# audible.net
KiCad netlist of a schematic drawn in EAGLE
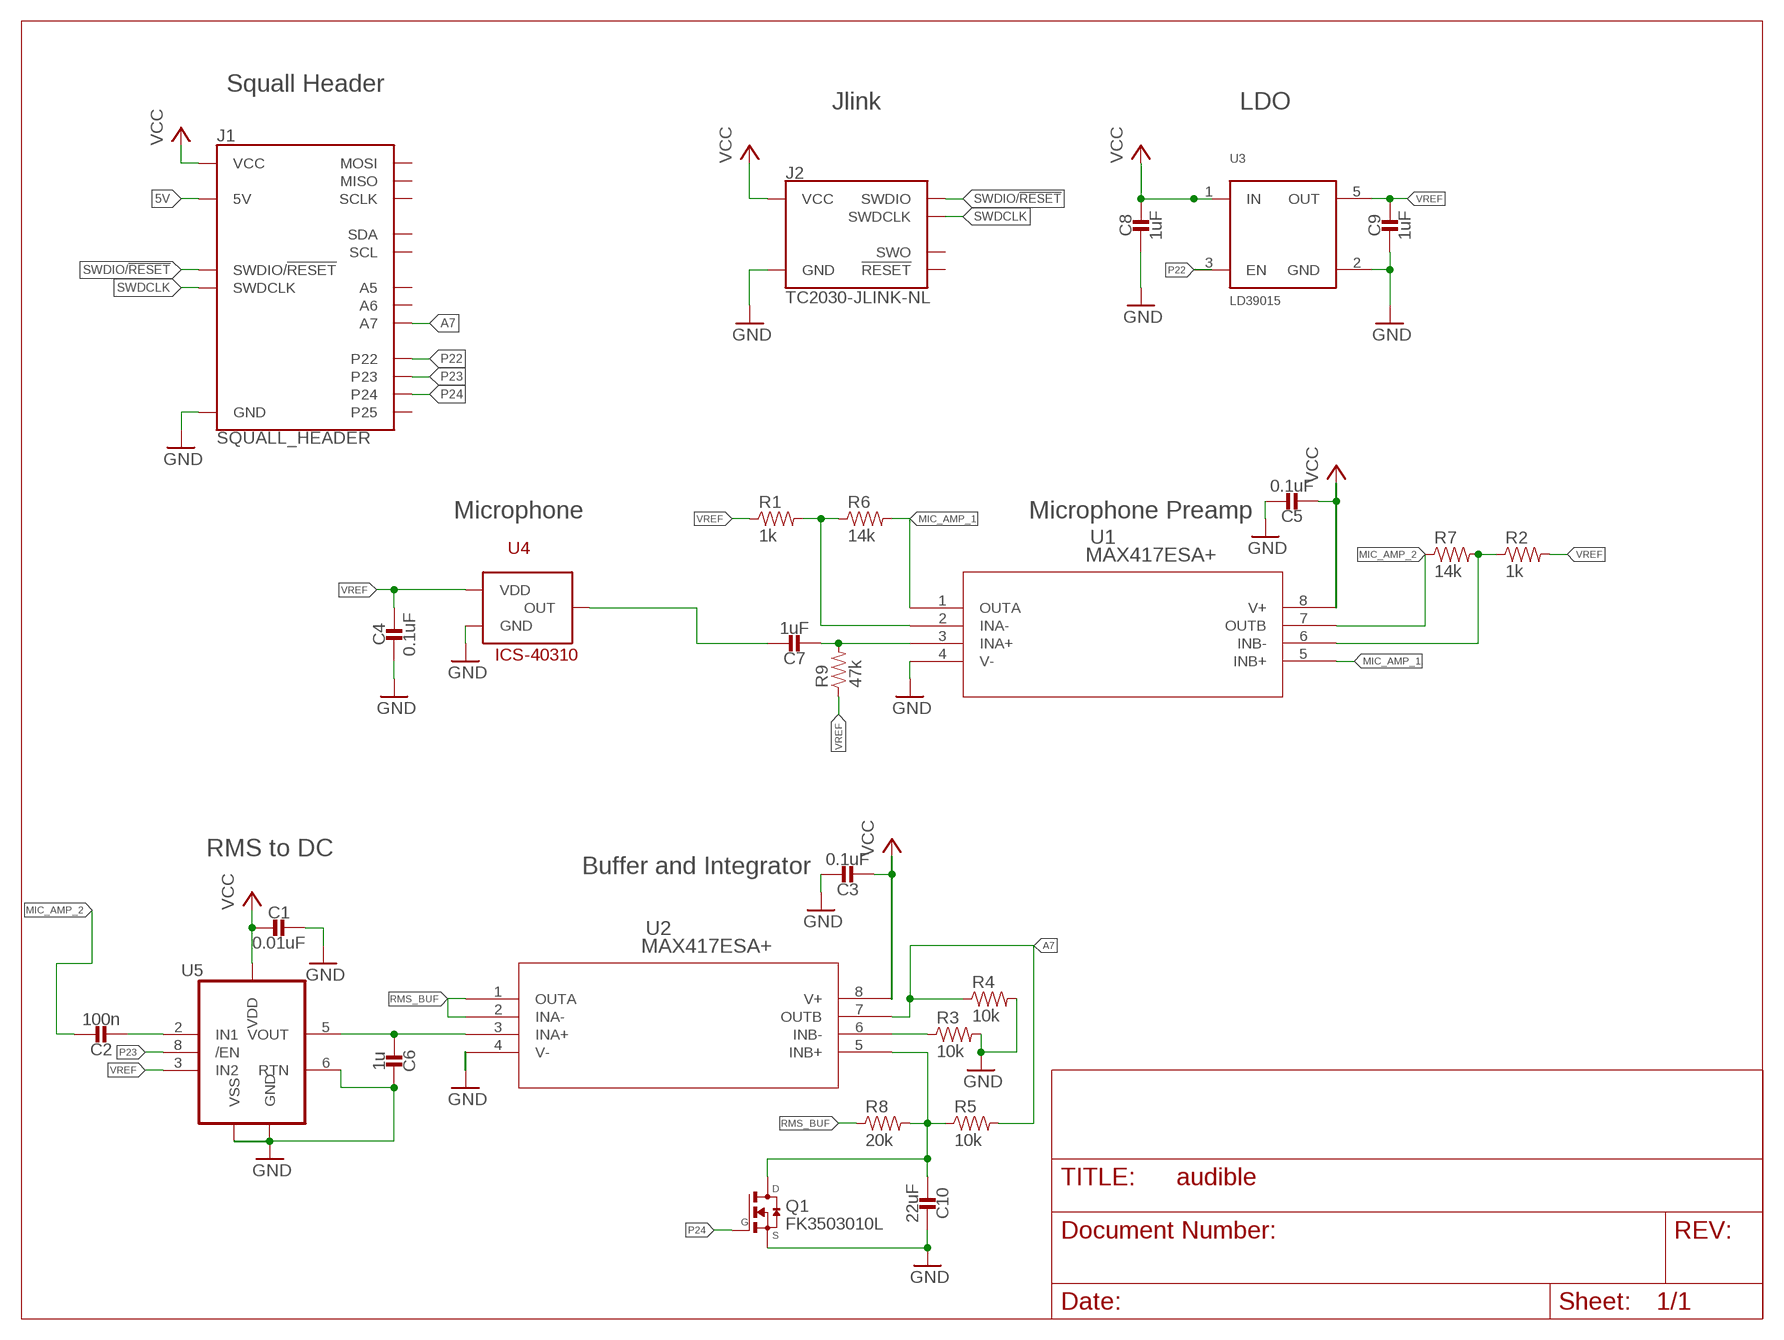
[diagram p0: schematic, sheet 1]

(export (version "E")
  (design (tool "Eeschema 10.0.6"))
  (components
    (comp (ref "C1")
      (value "0.01uF")
      (footprint "eagle-import:0402_CAP")
      (libsource (lib "eagle-import") (part "CAPACITOR"))
    )
    (comp (ref "C2")
      (value "100n")
      (footprint "eagle-import:0402_CAP")
      (libsource (lib "eagle-import") (part "CAPACITOR"))
    )
    (comp (ref "C3")
      (value "0.1uF")
      (footprint "eagle-import:0402_CAP")
      (libsource (lib "eagle-import") (part "CAPACITOR"))
    )
    (comp (ref "C4")
      (value "0.1uF")
      (footprint "eagle-import:0402_CAP")
      (libsource (lib "eagle-import") (part "CAPACITOR"))
    )
    (comp (ref "C5")
      (value "0.1uF")
      (footprint "eagle-import:0402_CAP")
      (libsource (lib "eagle-import") (part "CAPACITOR"))
    )
    (comp (ref "C6")
      (value "1u")
      (footprint "eagle-import:0402_CAP")
      (libsource (lib "eagle-import") (part "CAPACITOR"))
    )
    (comp (ref "C7")
      (value "1uF")
      (footprint "eagle-import:0402_CAP")
      (libsource (lib "eagle-import") (part "CAPACITOR"))
    )
    (comp (ref "C8")
      (value "1uF")
      (footprint "eagle-import:0402_CAP")
      (libsource (lib "eagle-import") (part "CAPACITOR"))
    )
    (comp (ref "C9")
      (value "1uF")
      (footprint "eagle-import:0402_CAP")
      (libsource (lib "eagle-import") (part "CAPACITOR"))
    )
    (comp (ref "C10")
      (value "22uF")
      (footprint "eagle-import:0402_CAP")
      (libsource (lib "eagle-import") (part "CAPACITOR"))
    )
    (comp (ref "J1")
      (value "SQUALL_HEADER")
      (footprint "eagle-import:SQUALL_HEADER")
      (libsource (lib "eagle-import") (part "SQUALL_HEADER"))
    )
    (comp (ref "J2")
      (value "TC2030-JLINK-NL")
      (footprint "eagle-import:TC2030-IDC-NL")
      (libsource (lib "eagle-import") (part "TC2030-JLINK-NL"))
    )
    (comp (ref "Q1")
      (value "FK3503010L")
      (footprint "eagle-import:SC85")
      (libsource (lib "eagle-import") (part "FK3503010L"))
    )
    (comp (ref "R1")
      (value "1k")
      (footprint "eagle-import:0402_RES")
      (libsource (lib "eagle-import") (part "RESISTOR0402_RES"))
    )
    (comp (ref "R2")
      (value "1k")
      (footprint "eagle-import:0402_RES")
      (libsource (lib "eagle-import") (part "RESISTOR0402_RES"))
    )
    (comp (ref "R3")
      (value "10k")
      (footprint "eagle-import:0402_RES")
      (libsource (lib "eagle-import") (part "RESISTOR0402_RES"))
    )
    (comp (ref "R4")
      (value "10k")
      (footprint "eagle-import:0402_RES")
      (libsource (lib "eagle-import") (part "RESISTOR0402_RES"))
    )
    (comp (ref "R5")
      (value "10k")
      (footprint "eagle-import:0402_RES")
      (libsource (lib "eagle-import") (part "RESISTOR0402_RES"))
    )
    (comp (ref "R6")
      (value "14k")
      (footprint "eagle-import:0402_RES")
      (libsource (lib "eagle-import") (part "RESISTOR0402_RES"))
    )
    (comp (ref "R7")
      (value "14k")
      (footprint "eagle-import:0402_RES")
      (libsource (lib "eagle-import") (part "RESISTOR0402_RES"))
    )
    (comp (ref "R8")
      (value "20k")
      (footprint "eagle-import:0402_RES")
      (libsource (lib "eagle-import") (part "RESISTOR0402_RES"))
    )
    (comp (ref "R9")
      (value "47k")
      (footprint "eagle-import:0402_RES")
      (libsource (lib "eagle-import") (part "RESISTOR0402_RES"))
    )
    (comp (ref "U1")
      (value "MAX417ESA+")
      (footprint "eagle-import:21-0041B_8")
      (fields (field (name "MANUFACTURER_PART_NUMBER") "max417esa+"))
      (libsource (lib "eagle-import") (part "MAX417ESA+"))
    )
    (comp (ref "U2")
      (value "MAX417ESA+")
      (footprint "eagle-import:21-0041B_8")
      (fields (field (name "MANUFACTURER_PART_NUMBER") "max417esa+"))
      (libsource (lib "eagle-import") (part "MAX417ESA+"))
    )
    (comp (ref "U3")
      (value "LD39015")
      (footprint "eagle-import:SOT-23-5")
      (libsource (lib "eagle-import") (part "LD39015"))
    )
    (comp (ref "U4")
      (value "ICS-40310")
      (footprint "eagle-import:LGA_CAV3")
      (libsource (lib "eagle-import") (part "ICS-40310"))
    )
    (comp (ref "U5")
      (value "LTC1966CMS8")
      (footprint "eagle-import:MSOP8")
      (libsource (lib "eagle-import") (part "LTC1966MS8C"))
    )
  )
  (nets
    (net (code "1") (name "/SWDIO{slash}~{RESET}") (class "Default")
      (node (ref "J1") (pin "B4") (pinfunction "SWDIO/~{RESET}_B4") (pintype "bidirectional"))
      (node (ref "J2") (pin "2") (pinfunction "SWDIO_2") (pintype "bidirectional"))
    )
    (net (code "2") (name "5V") (class "Default")
      (node (ref "J1") (pin "A5") (pinfunction "5V_A5") (pintype "bidirectional"))
      (node (ref "J1") (pin "A7") (pinfunction "5V_A7") (pintype "bidirectional"))
    )
    (net (code "3") (name "A7") (class "Default")
      (node (ref "J1") (pin "B5") (pinfunction "A7_B5") (pintype "bidirectional"))
      (node (ref "R4") (pin "1") (pinfunction "1_1") (pintype "passive"))
      (node (ref "R5") (pin "2") (pinfunction "2_2") (pintype "passive"))
      (node (ref "U2") (pin "7") (pinfunction "OUTB_7") (pintype "output"))
    )
    (net (code "4") (name "GND") (class "Default")
      (node (ref "C1") (pin "1") (pinfunction "1_1") (pintype "bidirectional"))
      (node (ref "C10") (pin "1") (pinfunction "1_1") (pintype "bidirectional"))
      (node (ref "C3") (pin "1") (pinfunction "1_1") (pintype "bidirectional"))
      (node (ref "C4") (pin "2") (pinfunction "2_2") (pintype "bidirectional"))
      (node (ref "C5") (pin "1") (pinfunction "1_1") (pintype "bidirectional"))
      (node (ref "C6") (pin "1") (pinfunction "1_1") (pintype "bidirectional"))
      (node (ref "C8") (pin "2") (pinfunction "2_2") (pintype "bidirectional"))
      (node (ref "C9") (pin "2") (pinfunction "2_2") (pintype "bidirectional"))
      (node (ref "J1") (pin "A10") (pinfunction "GND_A10") (pintype "bidirectional"))
      (node (ref "J1") (pin "A9") (pinfunction "GND_A9") (pintype "bidirectional"))
      (node (ref "J2") (pin "5") (pinfunction "GND_5") (pintype "bidirectional"))
      (node (ref "Q1") (pin "2") (pinfunction "S_2") (pintype "passive"))
      (node (ref "R3") (pin "2") (pinfunction "2_2") (pintype "passive"))
      (node (ref "R4") (pin "2") (pinfunction "2_2") (pintype "passive"))
      (node (ref "U1") (pin "4") (pinfunction "V-_4") (pintype "power_in"))
      (node (ref "U2") (pin "4") (pinfunction "V-_4") (pintype "power_in"))
      (node (ref "U3") (pin "2") (pinfunction "GND_2") (pintype "bidirectional"))
      (node (ref "U4") (pin "P$2") (pinfunction "GND_P$2") (pintype "bidirectional"))
      (node (ref "U5") (pin "1") (pinfunction "GND_1") (pintype "bidirectional"))
      (node (ref "U5") (pin "4") (pinfunction "VSS_4") (pintype "bidirectional"))
      (node (ref "U5") (pin "6") (pinfunction "RTN_6") (pintype "passive"))
    )
    (net (code "5") (name "MIC_AMP_1") (class "Default")
      (node (ref "R6") (pin "2") (pinfunction "2_2") (pintype "passive"))
      (node (ref "U1") (pin "1") (pinfunction "OUTA_1") (pintype "output"))
      (node (ref "U1") (pin "5") (pinfunction "INB+_5") (pintype "input"))
    )
    (net (code "6") (name "MIC_AMP_2") (class "Default")
      (node (ref "C2") (pin "1") (pinfunction "1_1") (pintype "bidirectional"))
      (node (ref "R7") (pin "1") (pinfunction "1_1") (pintype "passive"))
      (node (ref "U1") (pin "7") (pinfunction "OUTB_7") (pintype "output"))
    )
    (net (code "7") (name "Net-(Q1-D)") (class "Default")
      (node (ref "C10") (pin "2") (pinfunction "2_2") (pintype "bidirectional"))
      (node (ref "Q1") (pin "3") (pinfunction "D_3") (pintype "passive"))
      (node (ref "R5") (pin "1") (pinfunction "1_1") (pintype "passive"))
      (node (ref "R8") (pin "2") (pinfunction "2_2") (pintype "passive"))
      (node (ref "U2") (pin "5") (pinfunction "INB+_5") (pintype "input"))
    )
    (net (code "8") (name "Net-(U1-INA+)") (class "Default")
      (node (ref "C7") (pin "2") (pinfunction "2_2") (pintype "bidirectional"))
      (node (ref "R9") (pin "2") (pinfunction "2_2") (pintype "passive"))
      (node (ref "U1") (pin "3") (pinfunction "INA+_3") (pintype "input"))
    )
    (net (code "9") (name "Net-(U1-INA-)") (class "Default")
      (node (ref "R1") (pin "2") (pinfunction "2_2") (pintype "passive"))
      (node (ref "R6") (pin "1") (pinfunction "1_1") (pintype "passive"))
      (node (ref "U1") (pin "2") (pinfunction "INA-_2") (pintype "input"))
    )
    (net (code "10") (name "Net-(U1-INB-)") (class "Default")
      (node (ref "R2") (pin "1") (pinfunction "1_1") (pintype "passive"))
      (node (ref "R7") (pin "2") (pinfunction "2_2") (pintype "passive"))
      (node (ref "U1") (pin "6") (pinfunction "INB-_6") (pintype "input"))
    )
    (net (code "11") (name "Net-(U2-INA+)") (class "Default")
      (node (ref "C6") (pin "2") (pinfunction "2_2") (pintype "bidirectional"))
      (node (ref "U2") (pin "3") (pinfunction "INA+_3") (pintype "input"))
      (node (ref "U5") (pin "5") (pinfunction "VOUT_5") (pintype "output"))
    )
    (net (code "12") (name "Net-(U2-INB-)") (class "Default")
      (node (ref "R3") (pin "1") (pinfunction "1_1") (pintype "passive"))
      (node (ref "U2") (pin "6") (pinfunction "INB-_6") (pintype "input"))
    )
    (net (code "13") (name "Net-(U4-OUT)") (class "Default")
      (node (ref "C7") (pin "1") (pinfunction "1_1") (pintype "bidirectional"))
      (node (ref "U4") (pin "P$1") (pinfunction "OUT_P$1") (pintype "bidirectional"))
    )
    (net (code "14") (name "Net-(U5-IN1)") (class "Default")
      (node (ref "C2") (pin "2") (pinfunction "2_2") (pintype "bidirectional"))
      (node (ref "U5") (pin "2") (pinfunction "IN1_2") (pintype "input"))
    )
    (net (code "15") (name "P22") (class "Default")
      (node (ref "J1") (pin "A2") (pinfunction "P22_A2") (pintype "bidirectional"))
      (node (ref "U3") (pin "3") (pinfunction "EN_3") (pintype "bidirectional"))
    )
    (net (code "16") (name "P23") (class "Default")
      (node (ref "J1") (pin "A4") (pinfunction "P23_A4") (pintype "bidirectional"))
      (node (ref "U5") (pin "8") (pinfunction "/EN_8") (pintype "input"))
    )
    (net (code "17") (name "P24") (class "Default")
      (node (ref "J1") (pin "A6") (pinfunction "P24_A6") (pintype "bidirectional"))
      (node (ref "Q1") (pin "1") (pinfunction "G_1") (pintype "passive"))
    )
    (net (code "18") (name "RMS_BUF") (class "Default")
      (node (ref "R8") (pin "1") (pinfunction "1_1") (pintype "passive"))
      (node (ref "U2") (pin "1") (pinfunction "OUTA_1") (pintype "output"))
      (node (ref "U2") (pin "2") (pinfunction "INA-_2") (pintype "input"))
    )
    (net (code "19") (name "SWDCLK") (class "Default")
      (node (ref "J1") (pin "B2") (pinfunction "SWDCLK_B2") (pintype "bidirectional"))
      (node (ref "J2") (pin "4") (pinfunction "SWDCLK_4") (pintype "bidirectional"))
    )
    (net (code "20") (name "VCC") (class "Default")
      (node (ref "C1") (pin "2") (pinfunction "2_2") (pintype "bidirectional"))
      (node (ref "C3") (pin "2") (pinfunction "2_2") (pintype "bidirectional"))
      (node (ref "C5") (pin "2") (pinfunction "2_2") (pintype "bidirectional"))
      (node (ref "C8") (pin "1") (pinfunction "1_1") (pintype "bidirectional"))
      (node (ref "J1") (pin "A1") (pinfunction "VCC_A1") (pintype "bidirectional"))
      (node (ref "J1") (pin "A3") (pinfunction "VCC_A3") (pintype "bidirectional"))
      (node (ref "J2") (pin "1") (pinfunction "VCC_1") (pintype "bidirectional"))
      (node (ref "U1") (pin "8") (pinfunction "V+_8") (pintype "power_in"))
      (node (ref "U2") (pin "8") (pinfunction "V+_8") (pintype "power_in"))
      (node (ref "U3") (pin "1") (pinfunction "IN_1") (pintype "bidirectional"))
      (node (ref "U5") (pin "7") (pinfunction "VDD_7") (pintype "bidirectional"))
    )
    (net (code "21") (name "VREF") (class "Default")
      (node (ref "C4") (pin "1") (pinfunction "1_1") (pintype "bidirectional"))
      (node (ref "C9") (pin "1") (pinfunction "1_1") (pintype "bidirectional"))
      (node (ref "R1") (pin "1") (pinfunction "1_1") (pintype "passive"))
      (node (ref "R2") (pin "2") (pinfunction "2_2") (pintype "passive"))
      (node (ref "R9") (pin "1") (pinfunction "1_1") (pintype "passive"))
      (node (ref "U3") (pin "5") (pinfunction "OUT_5") (pintype "bidirectional"))
      (node (ref "U4") (pin "P$3") (pinfunction "VDD_P$3") (pintype "bidirectional"))
      (node (ref "U5") (pin "3") (pinfunction "IN2_3") (pintype "input"))
    )
    (net (code "22") (name "unconnected-(J1-A5-PadB9)") (class "Default")
      (node (ref "J1") (pin "B9") (pinfunction "A5_B9") (pintype "bidirectional"))
    )
    (net (code "23") (name "unconnected-(J1-A6-PadB7)") (class "Default")
      (node (ref "J1") (pin "B7") (pinfunction "A6_B7") (pintype "bidirectional"))
    )
    (net (code "24") (name "unconnected-(J1-MISO-PadB8)") (class "Default")
      (node (ref "J1") (pin "B8") (pinfunction "MISO_B8") (pintype "bidirectional"))
    )
    (net (code "25") (name "unconnected-(J1-MOSI-PadB6)") (class "Default")
      (node (ref "J1") (pin "B6") (pinfunction "MOSI_B6") (pintype "bidirectional"))
    )
    (net (code "26") (name "unconnected-(J1-P25-PadA8)") (class "Default")
      (node (ref "J1") (pin "A8") (pinfunction "P25_A8") (pintype "bidirectional"))
    )
    (net (code "27") (name "unconnected-(J1-SCL-PadB3)") (class "Default")
      (node (ref "J1") (pin "B3") (pinfunction "SCL_B3") (pintype "bidirectional"))
    )
    (net (code "28") (name "unconnected-(J1-SCLK-PadB10)") (class "Default")
      (node (ref "J1") (pin "B10") (pinfunction "SCLK_B10") (pintype "bidirectional"))
    )
    (net (code "29") (name "unconnected-(J1-SDA-PadB1)") (class "Default")
      (node (ref "J1") (pin "B1") (pinfunction "SDA_B1") (pintype "bidirectional"))
    )
    (net (code "30") (name "unconnected-(J2-SWO-Pad6)") (class "Default")
      (node (ref "J2") (pin "6") (pinfunction "SWO_6") (pintype "bidirectional"))
    )
    (net (code "31") (name "unconnected-(J2-~{RESET}-Pad3)") (class "Default")
      (node (ref "J2") (pin "3") (pinfunction "~{RESET}_3") (pintype "bidirectional"))
    )
  )
)
